# pedometer.net
KiCad netlist of a schematic drawn in EAGLE
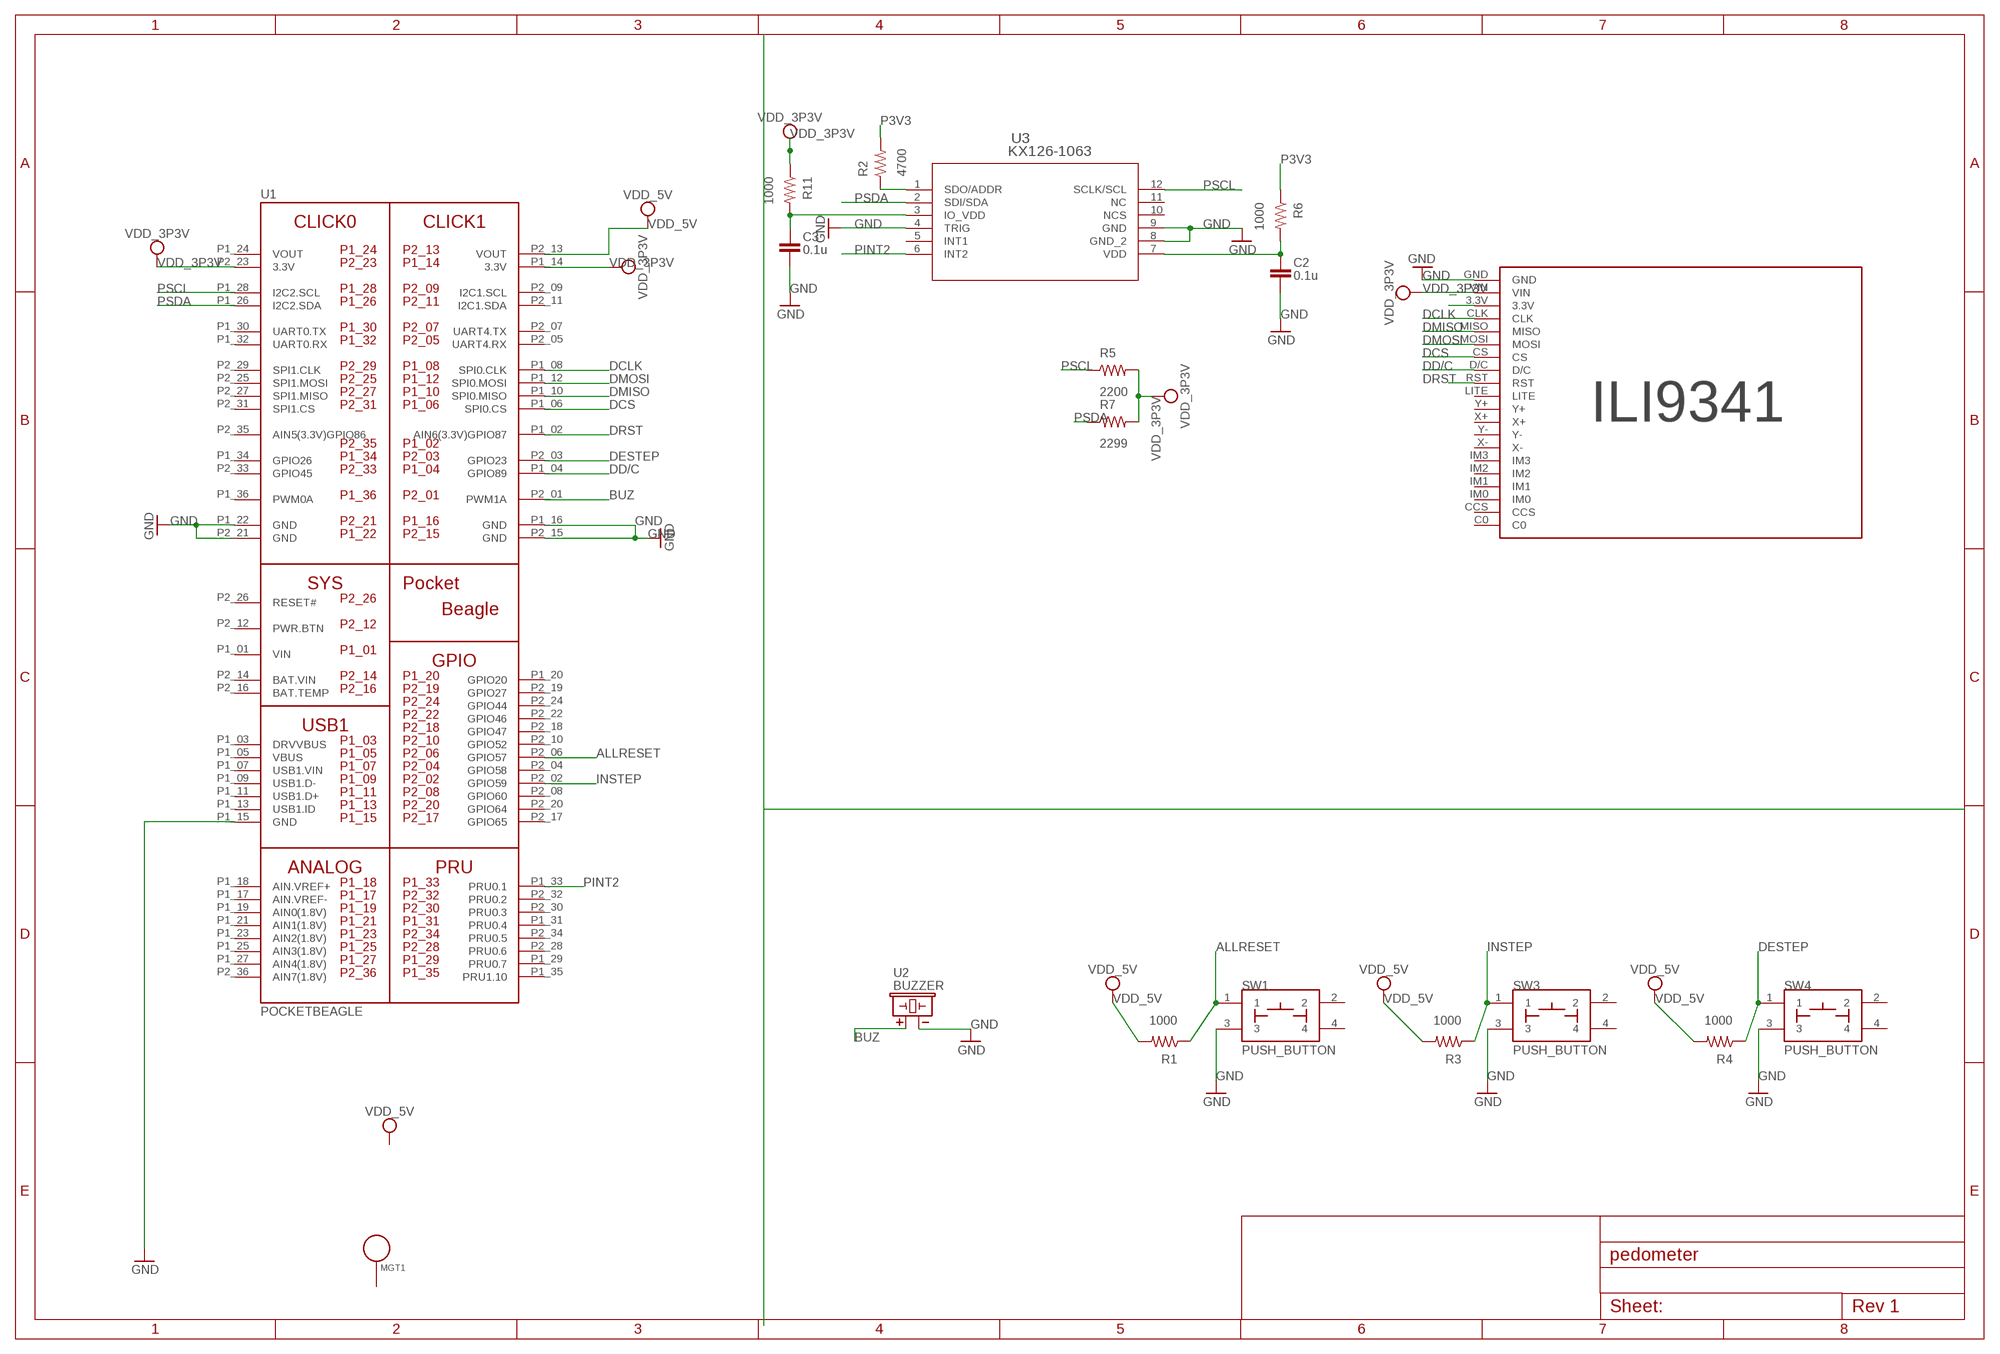
[diagram p0: schematic, sheet 1]

(export (version "E")
  (design (tool "Eeschema 10.0.6"))
  (components
    (comp (ref "B2")
      (value "ILI9341")
      (footprint "eagle-import:ILI9341")
      (libsource (lib "eagle-import") (part "ILI9341"))
    )
    (comp (ref "C2")
      (value "0.1u")
      (footprint "eagle-import:C0402")
      (libsource (lib "eagle-import") (part "C_C0402"))
    )
    (comp (ref "C3")
      (value "0.1u")
      (footprint "eagle-import:C0402")
      (libsource (lib "eagle-import") (part "C_C0402"))
    )
    (comp (ref "MGT1")
      (value "MOUNTING_HOLE")
      (footprint "eagle-import:MOUNTING_HOLE")
      (libsource (lib "eagle-import") (part "MOUNTING_HOLE"))
    )
    (comp (ref "R1")
      (value "1000")
      (footprint "eagle-import:R0805")
      (libsource (lib "eagle-import") (part "R_R0805"))
    )
    (comp (ref "R2")
      (value "4700")
      (footprint "eagle-import:R0603")
      (libsource (lib "eagle-import") (part "R_R0603"))
    )
    (comp (ref "R3")
      (value "1000")
      (footprint "eagle-import:R0805")
      (libsource (lib "eagle-import") (part "R_R0805"))
    )
    (comp (ref "R4")
      (value "1000")
      (footprint "eagle-import:R0805")
      (libsource (lib "eagle-import") (part "R_R0805"))
    )
    (comp (ref "R5")
      (value "2200")
      (footprint "eagle-import:R0603")
      (libsource (lib "eagle-import") (part "R_R0603"))
    )
    (comp (ref "R6")
      (value "1000")
      (footprint "eagle-import:R0603")
      (libsource (lib "eagle-import") (part "R_R0603"))
    )
    (comp (ref "R7")
      (value "2299")
      (footprint "eagle-import:R0603")
      (libsource (lib "eagle-import") (part "R_R0603"))
    )
    (comp (ref "R11")
      (value "1000")
      (footprint "eagle-import:R0603")
      (libsource (lib "eagle-import") (part "R_R0603"))
    )
    (comp (ref "SW1")
      (value "PUSH_BUTTON")
      (footprint "eagle-import:BUTTON_12.5MM")
      (libsource (lib "eagle-import") (part "PUSH_BUTTON"))
    )
    (comp (ref "SW3")
      (value "PUSH_BUTTON")
      (footprint "eagle-import:BUTTON_12.5MM")
      (libsource (lib "eagle-import") (part "PUSH_BUTTON"))
    )
    (comp (ref "SW4")
      (value "PUSH_BUTTON")
      (footprint "eagle-import:BUTTON_12.5MM")
      (libsource (lib "eagle-import") (part "PUSH_BUTTON"))
    )
    (comp (ref "U1")
      (value "POCKETBEAGLE")
      (footprint "eagle-import:POCKETBEAGLE")
      (libsource (lib "eagle-import") (part "POCKETBEAGLE"))
    )
    (comp (ref "U2")
      (value "BUZZER")
      (footprint "eagle-import:BUZZER_6.5MM")
      (libsource (lib "eagle-import") (part "BUZZER"))
    )
    (comp (ref "U3")
      (value "KX126-1063")
      (footprint "eagle-import:LGA12_2X2X0P9_KNX")
      (fields (field (name "COPYRIGHT") "Copyright (C) 2021 Ultra Librarian. All rights reserved."))
      (libsource (lib "eagle-import") (part "KX126-1063"))
    )
  )
  (nets
    (net (code "1") (name "/ALLRESET") (class "Default")
      (node (ref "R1") (pin "1") (pinfunction "1_1") (pintype "passive"))
      (node (ref "SW1") (pin "1") (pinfunction "1_1") (pintype "bidirectional"))
      (node (ref "U1") (pin "P2_06") (pinfunction "GPIO57_P2_06") (pintype "bidirectional"))
    )
    (net (code "2") (name "/BAT.VIN") (class "Default")
      (node (ref "U1") (pin "P2_14") (pinfunction "BAT.VIN_P2_14") (pintype "power_in"))
    )
    (net (code "3") (name "/BUZ") (class "Default")
      (node (ref "U1") (pin "P2_01") (pinfunction "PWM1A_P2_01") (pintype "bidirectional"))
      (node (ref "U2") (pin "+") (pinfunction "+_+") (pintype "passive"))
    )
    (net (code "4") (name "/DCLK") (class "Default")
      (node (ref "B2") (pin "CLK") (pinfunction "CLK_CLK") (pintype "bidirectional"))
      (node (ref "U1") (pin "P1_08") (pinfunction "SPI0.CLK_P1_08") (pintype "bidirectional"))
    )
    (net (code "5") (name "/DCS") (class "Default")
      (node (ref "B2") (pin "CS") (pinfunction "CS_CS") (pintype "bidirectional"))
      (node (ref "U1") (pin "P1_06") (pinfunction "SPI0.CS_P1_06") (pintype "bidirectional"))
    )
    (net (code "6") (name "/DD{slash}C") (class "Default")
      (node (ref "B2") (pin "D/C") (pinfunction "D/C_D/C") (pintype "bidirectional"))
      (node (ref "U1") (pin "P1_04") (pinfunction "GPIO89_P1_04") (pintype "bidirectional"))
    )
    (net (code "7") (name "/DESTEP") (class "Default")
      (node (ref "R4") (pin "1") (pinfunction "1_1") (pintype "passive"))
      (node (ref "SW4") (pin "1") (pinfunction "1_1") (pintype "bidirectional"))
      (node (ref "U1") (pin "P2_03") (pinfunction "GPIO23_P2_03") (pintype "bidirectional"))
    )
    (net (code "8") (name "/DMISO") (class "Default")
      (node (ref "B2") (pin "MISO") (pinfunction "MISO_MISO") (pintype "bidirectional"))
      (node (ref "U1") (pin "P1_10") (pinfunction "SPI0.MISO_P1_10") (pintype "bidirectional"))
    )
    (net (code "9") (name "/DMOSI") (class "Default")
      (node (ref "B2") (pin "MOSI") (pinfunction "MOSI_MOSI") (pintype "bidirectional"))
      (node (ref "U1") (pin "P1_12") (pinfunction "SPI0.MOSI_P1_12") (pintype "bidirectional"))
    )
    (net (code "10") (name "/DRST") (class "Default")
      (node (ref "B2") (pin "RST") (pinfunction "RST_RST") (pintype "bidirectional"))
      (node (ref "U1") (pin "P1_02") (pinfunction "AIN6(3.3V)GPIO87_P1_02") (pintype "bidirectional"))
    )
    (net (code "11") (name "/INSTEP") (class "Default")
      (node (ref "R3") (pin "1") (pinfunction "1_1") (pintype "passive"))
      (node (ref "SW3") (pin "1") (pinfunction "1_1") (pintype "bidirectional"))
      (node (ref "U1") (pin "P2_02") (pinfunction "GPIO59_P2_02") (pintype "bidirectional"))
    )
    (net (code "12") (name "/P3V3") (class "Default")
      (node (ref "R2") (pin "2") (pinfunction "2_2") (pintype "passive"))
      (node (ref "R6") (pin "1") (pinfunction "1_1") (pintype "passive"))
    )
    (net (code "13") (name "/PINT2") (class "Default")
      (node (ref "U1") (pin "P1_33") (pinfunction "PRU0.1_P1_33") (pintype "bidirectional"))
      (node (ref "U3") (pin "6") (pinfunction "INT2_6") (pintype "output"))
    )
    (net (code "14") (name "/PSCL") (class "Default")
      (node (ref "R5") (pin "1") (pinfunction "1_1") (pintype "passive"))
      (node (ref "U1") (pin "P1_28") (pinfunction "I2C2.SCL_P1_28") (pintype "bidirectional"))
      (node (ref "U3") (pin "12") (pinfunction "SCLK/SCL_12") (pintype "input"))
    )
    (net (code "15") (name "/PSDA") (class "Default")
      (node (ref "R7") (pin "1") (pinfunction "1_1") (pintype "passive"))
      (node (ref "U1") (pin "P1_26") (pinfunction "I2C2.SDA_P1_26") (pintype "bidirectional"))
      (node (ref "U3") (pin "2") (pinfunction "SDI/SDA_2") (pintype "input"))
    )
    (net (code "16") (name "/VIN") (class "Default")
      (node (ref "U1") (pin "P1_01") (pinfunction "VIN_P1_01") (pintype "power_in"))
    )
    (net (code "17") (name "/VOUT") (class "Default")
      (node (ref "U1") (pin "P1_24") (pinfunction "VOUT_P1_24") (pintype "power_in"))
    )
    (net (code "18") (name "GND") (class "Default")
      (node (ref "B2") (pin "GND") (pinfunction "GND_GND") (pintype "bidirectional"))
      (node (ref "C2") (pin "2") (pinfunction "2_2") (pintype "passive"))
      (node (ref "C3") (pin "2") (pinfunction "2_2") (pintype "passive"))
      (node (ref "SW1") (pin "3") (pinfunction "3_3") (pintype "bidirectional"))
      (node (ref "SW3") (pin "3") (pinfunction "3_3") (pintype "bidirectional"))
      (node (ref "SW4") (pin "3") (pinfunction "3_3") (pintype "bidirectional"))
      (node (ref "U1") (pin "P1_15") (pinfunction "GND_P1_15") (pintype "bidirectional"))
      (node (ref "U1") (pin "P1_16") (pinfunction "GND_P1_16") (pintype "power_in"))
      (node (ref "U1") (pin "P1_22") (pinfunction "GND_P1_22") (pintype "power_in"))
      (node (ref "U1") (pin "P2_15") (pinfunction "GND_P2_15") (pintype "power_in"))
      (node (ref "U1") (pin "P2_21") (pinfunction "GND_P2_21") (pintype "power_in"))
      (node (ref "U2") (pin "-") (pinfunction "-_-") (pintype "passive"))
      (node (ref "U3") (pin "4") (pinfunction "TRIG_4") (pintype "input"))
      (node (ref "U3") (pin "8") (pinfunction "GND_2_8") (pintype "passive"))
      (node (ref "U3") (pin "9") (pinfunction "GND_9") (pintype "passive"))
    )
    (net (code "19") (name "Net-(U3-IO_VDD)") (class "Default")
      (node (ref "C3") (pin "1") (pinfunction "1_1") (pintype "passive"))
      (node (ref "R11") (pin "2") (pinfunction "2_2") (pintype "passive"))
      (node (ref "U3") (pin "3") (pinfunction "IO_VDD_3") (pintype "power_in"))
    )
    (net (code "20") (name "Net-(U3-SDO{slash}ADDR)") (class "Default")
      (node (ref "R2") (pin "1") (pinfunction "1_1") (pintype "passive"))
      (node (ref "U3") (pin "1") (pinfunction "SDO/ADDR_1") (pintype "input"))
    )
    (net (code "21") (name "Net-(U3-VDD)") (class "Default")
      (node (ref "C2") (pin "1") (pinfunction "1_1") (pintype "passive"))
      (node (ref "R6") (pin "2") (pinfunction "2_2") (pintype "passive"))
      (node (ref "U3") (pin "7") (pinfunction "VDD_7") (pintype "power_in"))
    )
    (net (code "22") (name "VDD_3P3V") (class "Default")
      (node (ref "B2") (pin "VIN") (pinfunction "VIN_VIN") (pintype "bidirectional"))
      (node (ref "R11") (pin "1") (pinfunction "1_1") (pintype "passive"))
      (node (ref "R5") (pin "2") (pinfunction "2_2") (pintype "passive"))
      (node (ref "R7") (pin "2") (pinfunction "2_2") (pintype "passive"))
      (node (ref "U1") (pin "P1_14") (pinfunction "3.3V_P1_14") (pintype "power_in"))
      (node (ref "U1") (pin "P2_23") (pinfunction "3.3V_P2_23") (pintype "power_in"))
    )
    (net (code "23") (name "VDD_5V") (class "Default")
      (node (ref "R1") (pin "2") (pinfunction "2_2") (pintype "passive"))
      (node (ref "R3") (pin "2") (pinfunction "2_2") (pintype "passive"))
      (node (ref "R4") (pin "2") (pinfunction "2_2") (pintype "passive"))
      (node (ref "U1") (pin "P2_13") (pinfunction "VOUT_P2_13") (pintype "power_in"))
    )
    (net (code "24") (name "unconnected-(B2-Pad3.3V)") (class "Default")
      (node (ref "B2") (pin "3.3V") (pinfunction "3.3V_3.3V") (pintype "bidirectional"))
    )
    (net (code "25") (name "unconnected-(B2-PadC0)") (class "Default")
      (node (ref "B2") (pin "C0") (pinfunction "C0_C0") (pintype "bidirectional"))
    )
    (net (code "26") (name "unconnected-(B2-PadCCS)") (class "Default")
      (node (ref "B2") (pin "CCS") (pinfunction "CCS_CCS") (pintype "bidirectional"))
    )
    (net (code "27") (name "unconnected-(B2-PadIM0)") (class "Default")
      (node (ref "B2") (pin "IM0") (pinfunction "IM0_IM0") (pintype "bidirectional"))
    )
    (net (code "28") (name "unconnected-(B2-PadIM1)") (class "Default")
      (node (ref "B2") (pin "IM1") (pinfunction "IM1_IM1") (pintype "bidirectional"))
    )
    (net (code "29") (name "unconnected-(B2-PadIM2)") (class "Default")
      (node (ref "B2") (pin "IM2") (pinfunction "IM2_IM2") (pintype "bidirectional"))
    )
    (net (code "30") (name "unconnected-(B2-PadIM3)") (class "Default")
      (node (ref "B2") (pin "IM3") (pinfunction "IM3_IM3") (pintype "bidirectional"))
    )
    (net (code "31") (name "unconnected-(B2-PadLITE)") (class "Default")
      (node (ref "B2") (pin "LITE") (pinfunction "LITE_LITE") (pintype "bidirectional"))
    )
    (net (code "32") (name "unconnected-(B2-PadX+)") (class "Default")
      (node (ref "B2") (pin "X+") (pinfunction "X+_X+") (pintype "bidirectional"))
    )
    (net (code "33") (name "unconnected-(B2-PadX-)") (class "Default")
      (node (ref "B2") (pin "X-") (pinfunction "X-_X-") (pintype "bidirectional"))
    )
    (net (code "34") (name "unconnected-(B2-PadY+)") (class "Default")
      (node (ref "B2") (pin "Y+") (pinfunction "Y+_Y+") (pintype "bidirectional"))
    )
    (net (code "35") (name "unconnected-(B2-PadY-)") (class "Default")
      (node (ref "B2") (pin "Y-") (pinfunction "Y-_Y-") (pintype "bidirectional"))
    )
    (net (code "36") (name "unconnected-(MGT1-PadP$1)") (class "Default")
      (node (ref "MGT1") (pin "P$1") (pinfunction "P$1_P$1") (pintype "bidirectional"))
    )
    (net (code "37") (name "unconnected-(SW1-Pad2)") (class "Default")
      (node (ref "SW1") (pin "2") (pinfunction "2_2") (pintype "bidirectional"))
    )
    (net (code "38") (name "unconnected-(SW1-Pad4)") (class "Default")
      (node (ref "SW1") (pin "4") (pinfunction "4_4") (pintype "bidirectional"))
    )
    (net (code "39") (name "unconnected-(SW3-Pad2)") (class "Default")
      (node (ref "SW3") (pin "2") (pinfunction "2_2") (pintype "bidirectional"))
    )
    (net (code "40") (name "unconnected-(SW3-Pad4)") (class "Default")
      (node (ref "SW3") (pin "4") (pinfunction "4_4") (pintype "bidirectional"))
    )
    (net (code "41") (name "unconnected-(SW4-Pad2)") (class "Default")
      (node (ref "SW4") (pin "2") (pinfunction "2_2") (pintype "bidirectional"))
    )
    (net (code "42") (name "unconnected-(SW4-Pad4)") (class "Default")
      (node (ref "SW4") (pin "4") (pinfunction "4_4") (pintype "bidirectional"))
    )
    (net (code "43") (name "unconnected-(U1-AIN.VREF+-PadP1_18)") (class "Default")
      (node (ref "U1") (pin "P1_18") (pinfunction "AIN.VREF+_P1_18") (pintype "input"))
    )
    (net (code "44") (name "unconnected-(U1-AIN.VREF--PadP1_17)") (class "Default")
      (node (ref "U1") (pin "P1_17") (pinfunction "AIN.VREF-_P1_17") (pintype "input"))
    )
    (net (code "45") (name "unconnected-(U1-AIN0(1.8V)-PadP1_19)") (class "Default")
      (node (ref "U1") (pin "P1_19") (pinfunction "AIN0(1.8V)_P1_19") (pintype "input"))
    )
    (net (code "46") (name "unconnected-(U1-AIN1(1.8V)-PadP1_21)") (class "Default")
      (node (ref "U1") (pin "P1_21") (pinfunction "AIN1(1.8V)_P1_21") (pintype "input"))
    )
    (net (code "47") (name "unconnected-(U1-AIN2(1.8V)-PadP1_23)") (class "Default")
      (node (ref "U1") (pin "P1_23") (pinfunction "AIN2(1.8V)_P1_23") (pintype "input"))
    )
    (net (code "48") (name "unconnected-(U1-AIN3(1.8V)-PadP1_25)") (class "Default")
      (node (ref "U1") (pin "P1_25") (pinfunction "AIN3(1.8V)_P1_25") (pintype "input"))
    )
    (net (code "49") (name "unconnected-(U1-AIN4(1.8V)-PadP1_27)") (class "Default")
      (node (ref "U1") (pin "P1_27") (pinfunction "AIN4(1.8V)_P1_27") (pintype "input"))
    )
    (net (code "50") (name "unconnected-(U1-AIN5(3.3V)GPIO86-PadP2_35)") (class "Default")
      (node (ref "U1") (pin "P2_35") (pinfunction "AIN5(3.3V)GPIO86_P2_35") (pintype "bidirectional"))
    )
    (net (code "51") (name "unconnected-(U1-AIN7(1.8V)-PadP2_36)") (class "Default")
      (node (ref "U1") (pin "P2_36") (pinfunction "AIN7(1.8V)_P2_36") (pintype "input"))
    )
    (net (code "52") (name "unconnected-(U1-BAT.TEMP-PadP2_16)") (class "Default")
      (node (ref "U1") (pin "P2_16") (pinfunction "BAT.TEMP_P2_16") (pintype "input"))
    )
    (net (code "53") (name "unconnected-(U1-DRVVBUS-PadP1_03)") (class "Default")
      (node (ref "U1") (pin "P1_03") (pinfunction "DRVVBUS_P1_03") (pintype "bidirectional"))
    )
    (net (code "54") (name "unconnected-(U1-GPIO20-PadP1_20)") (class "Default")
      (node (ref "U1") (pin "P1_20") (pinfunction "GPIO20_P1_20") (pintype "bidirectional"))
    )
    (net (code "55") (name "unconnected-(U1-GPIO26-PadP1_34)") (class "Default")
      (node (ref "U1") (pin "P1_34") (pinfunction "GPIO26_P1_34") (pintype "bidirectional"))
    )
    (net (code "56") (name "unconnected-(U1-GPIO27-PadP2_19)") (class "Default")
      (node (ref "U1") (pin "P2_19") (pinfunction "GPIO27_P2_19") (pintype "bidirectional"))
    )
    (net (code "57") (name "unconnected-(U1-GPIO44-PadP2_24)") (class "Default")
      (node (ref "U1") (pin "P2_24") (pinfunction "GPIO44_P2_24") (pintype "bidirectional"))
    )
    (net (code "58") (name "unconnected-(U1-GPIO45-PadP2_33)") (class "Default")
      (node (ref "U1") (pin "P2_33") (pinfunction "GPIO45_P2_33") (pintype "bidirectional"))
    )
    (net (code "59") (name "unconnected-(U1-GPIO46-PadP2_22)") (class "Default")
      (node (ref "U1") (pin "P2_22") (pinfunction "GPIO46_P2_22") (pintype "bidirectional"))
    )
    (net (code "60") (name "unconnected-(U1-GPIO47-PadP2_18)") (class "Default")
      (node (ref "U1") (pin "P2_18") (pinfunction "GPIO47_P2_18") (pintype "bidirectional"))
    )
    (net (code "61") (name "unconnected-(U1-GPIO52-PadP2_10)") (class "Default")
      (node (ref "U1") (pin "P2_10") (pinfunction "GPIO52_P2_10") (pintype "bidirectional"))
    )
    (net (code "62") (name "unconnected-(U1-GPIO58-PadP2_04)") (class "Default")
      (node (ref "U1") (pin "P2_04") (pinfunction "GPIO58_P2_04") (pintype "bidirectional"))
    )
    (net (code "63") (name "unconnected-(U1-GPIO60-PadP2_08)") (class "Default")
      (node (ref "U1") (pin "P2_08") (pinfunction "GPIO60_P2_08") (pintype "bidirectional"))
    )
    (net (code "64") (name "unconnected-(U1-GPIO64-PadP2_20)") (class "Default")
      (node (ref "U1") (pin "P2_20") (pinfunction "GPIO64_P2_20") (pintype "bidirectional"))
    )
    (net (code "65") (name "unconnected-(U1-GPIO65-PadP2_17)") (class "Default")
      (node (ref "U1") (pin "P2_17") (pinfunction "GPIO65_P2_17") (pintype "bidirectional"))
    )
    (net (code "66") (name "unconnected-(U1-I2C1.SCL-PadP2_09)") (class "Default")
      (node (ref "U1") (pin "P2_09") (pinfunction "I2C1.SCL_P2_09") (pintype "bidirectional"))
    )
    (net (code "67") (name "unconnected-(U1-I2C1.SDA-PadP2_11)") (class "Default")
      (node (ref "U1") (pin "P2_11") (pinfunction "I2C1.SDA_P2_11") (pintype "bidirectional"))
    )
    (net (code "68") (name "unconnected-(U1-PRU0.2-PadP2_32)") (class "Default")
      (node (ref "U1") (pin "P2_32") (pinfunction "PRU0.2_P2_32") (pintype "bidirectional"))
    )
    (net (code "69") (name "unconnected-(U1-PRU0.3-PadP2_30)") (class "Default")
      (node (ref "U1") (pin "P2_30") (pinfunction "PRU0.3_P2_30") (pintype "bidirectional"))
    )
    (net (code "70") (name "unconnected-(U1-PRU0.4-PadP1_31)") (class "Default")
      (node (ref "U1") (pin "P1_31") (pinfunction "PRU0.4_P1_31") (pintype "bidirectional"))
    )
    (net (code "71") (name "unconnected-(U1-PRU0.5-PadP2_34)") (class "Default")
      (node (ref "U1") (pin "P2_34") (pinfunction "PRU0.5_P2_34") (pintype "bidirectional"))
    )
    (net (code "72") (name "unconnected-(U1-PRU0.6-PadP2_28)") (class "Default")
      (node (ref "U1") (pin "P2_28") (pinfunction "PRU0.6_P2_28") (pintype "bidirectional"))
    )
    (net (code "73") (name "unconnected-(U1-PRU0.7-PadP1_29)") (class "Default")
      (node (ref "U1") (pin "P1_29") (pinfunction "PRU0.7_P1_29") (pintype "bidirectional"))
    )
    (net (code "74") (name "unconnected-(U1-PRU1.10-PadP1_35)") (class "Default")
      (node (ref "U1") (pin "P1_35") (pinfunction "PRU1.10_P1_35") (pintype "bidirectional"))
    )
    (net (code "75") (name "unconnected-(U1-PWM0A-PadP1_36)") (class "Default")
      (node (ref "U1") (pin "P1_36") (pinfunction "PWM0A_P1_36") (pintype "bidirectional"))
    )
    (net (code "76") (name "unconnected-(U1-PWR.BTN-PadP2_12)") (class "Default")
      (node (ref "U1") (pin "P2_12") (pinfunction "PWR.BTN_P2_12") (pintype "input"))
    )
    (net (code "77") (name "unconnected-(U1-RESET#-PadP2_26)") (class "Default")
      (node (ref "U1") (pin "P2_26") (pinfunction "RESET#_P2_26") (pintype "input"))
    )
    (net (code "78") (name "unconnected-(U1-SPI1.CLK-PadP2_29)") (class "Default")
      (node (ref "U1") (pin "P2_29") (pinfunction "SPI1.CLK_P2_29") (pintype "bidirectional"))
    )
    (net (code "79") (name "unconnected-(U1-SPI1.CS-PadP2_31)") (class "Default")
      (node (ref "U1") (pin "P2_31") (pinfunction "SPI1.CS_P2_31") (pintype "bidirectional"))
    )
    (net (code "80") (name "unconnected-(U1-SPI1.MISO-PadP2_27)") (class "Default")
      (node (ref "U1") (pin "P2_27") (pinfunction "SPI1.MISO_P2_27") (pintype "bidirectional"))
    )
    (net (code "81") (name "unconnected-(U1-SPI1.MOSI-PadP2_25)") (class "Default")
      (node (ref "U1") (pin "P2_25") (pinfunction "SPI1.MOSI_P2_25") (pintype "bidirectional"))
    )
    (net (code "82") (name "unconnected-(U1-UART0.RX-PadP1_32)") (class "Default")
      (node (ref "U1") (pin "P1_32") (pinfunction "UART0.RX_P1_32") (pintype "bidirectional"))
    )
    (net (code "83") (name "unconnected-(U1-UART0.TX-PadP1_30)") (class "Default")
      (node (ref "U1") (pin "P1_30") (pinfunction "UART0.TX_P1_30") (pintype "bidirectional"))
    )
    (net (code "84") (name "unconnected-(U1-UART4.RX-PadP2_05)") (class "Default")
      (node (ref "U1") (pin "P2_05") (pinfunction "UART4.RX_P2_05") (pintype "bidirectional"))
    )
    (net (code "85") (name "unconnected-(U1-UART4.TX-PadP2_07)") (class "Default")
      (node (ref "U1") (pin "P2_07") (pinfunction "UART4.TX_P2_07") (pintype "bidirectional"))
    )
    (net (code "86") (name "unconnected-(U1-USB1.D+-PadP1_11)") (class "Default")
      (node (ref "U1") (pin "P1_11") (pinfunction "USB1.D+_P1_11") (pintype "bidirectional"))
    )
    (net (code "87") (name "unconnected-(U1-USB1.D--PadP1_09)") (class "Default")
      (node (ref "U1") (pin "P1_09") (pinfunction "USB1.D-_P1_09") (pintype "bidirectional"))
    )
    (net (code "88") (name "unconnected-(U1-USB1.ID-PadP1_13)") (class "Default")
      (node (ref "U1") (pin "P1_13") (pinfunction "USB1.ID_P1_13") (pintype "bidirectional"))
    )
    (net (code "89") (name "unconnected-(U1-USB1.VIN-PadP1_07)") (class "Default")
      (node (ref "U1") (pin "P1_07") (pinfunction "USB1.VIN_P1_07") (pintype "bidirectional"))
    )
    (net (code "90") (name "unconnected-(U1-VBUS-PadP1_05)") (class "Default")
      (node (ref "U1") (pin "P1_05") (pinfunction "VBUS_P1_05") (pintype "bidirectional"))
    )
    (net (code "91") (name "unconnected-(U3-INT1-Pad5)") (class "Default")
      (node (ref "U3") (pin "5") (pinfunction "INT1_5") (pintype "output"))
    )
    (net (code "92") (name "unconnected-(U3-NC-Pad11)") (class "Default")
      (node (ref "U3") (pin "11") (pinfunction "NC_11") (pintype "no_connect"))
    )
    (net (code "93") (name "unconnected-(U3-NCS-Pad10)") (class "Default")
      (node (ref "U3") (pin "10") (pinfunction "NCS_10") (pintype "input"))
    )
  )
)
